# Debug.net
KiCad netlist of a schematic drawn in Altium Designer
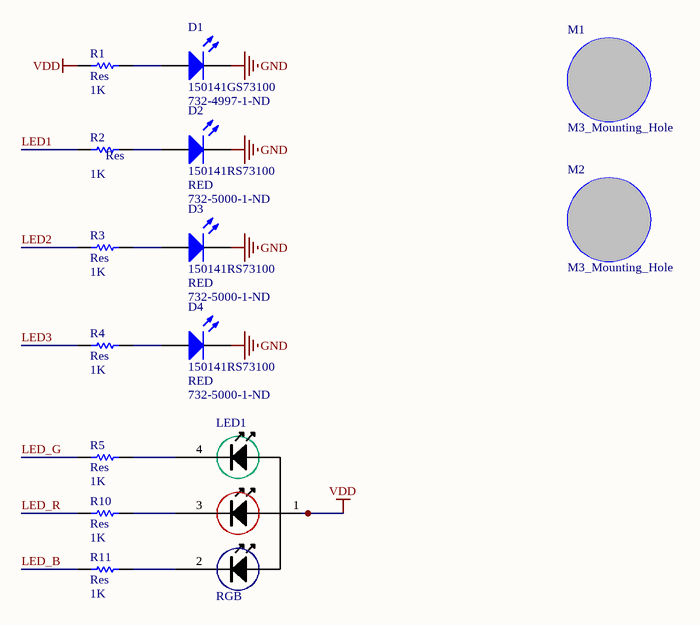
[diagram p0: Debug.SchDoc]

(export (version "E")
  (design (tool "Eeschema 10.0.6"))
  (components
    (comp (ref "D1")
      (value "150141GS73100")
      (footprint "150141RS73100")
      (description "Typical GREEN LED")
      (fields
        (field (name "MANUFACTURER") "Würth Elektronik (Wuerth Elektronik)")
        (field (name "SUPPLIER PART NUMBER 1") "732-4997-1-ND")
      )
      (libsource (lib "FC") (part "150141GS73100"))
    )
    (comp (ref "D2")
      (value "150141RS73100")
      (footprint "150141RS73100")
      (description "Typical RED LED")
      (fields
        (field (name "MANUFACTURER") "Würth Elektronik (Wuerth Elektronik)")
        (field (name "COLOUR") "RED")
        (field (name "SUPPLIER PART NUMBER 2") "732-5000-1-ND")
        (field (name "PUBLISHER") "Altium Limited")
      )
      (libsource (lib "FC") (part "150141RS73100"))
    )
    (comp (ref "D3")
      (value "150141RS73100")
      (footprint "150141RS73100")
      (description "Typical RED LED")
      (fields
        (field (name "MANUFACTURER") "Würth Elektronik (Wuerth Elektronik)")
        (field (name "COLOUR") "RED")
        (field (name "SUPPLIER PART NUMBER 2") "732-5000-1-ND")
        (field (name "PUBLISHER") "Altium Limited")
      )
      (libsource (lib "FC") (part "150141RS73100"))
    )
    (comp (ref "D4")
      (value "150141RS73100")
      (footprint "150141RS73100")
      (description "Typical RED LED")
      (fields
        (field (name "MANUFACTURER") "Würth Elektronik (Wuerth Elektronik)")
        (field (name "COLOUR") "RED")
        (field (name "SUPPLIER PART NUMBER 2") "732-5000-1-ND")
        (field (name "PUBLISHER") "Altium Limited")
      )
      (libsource (lib "FC") (part "150141RS73100"))
    )
    (comp (ref "LED1")
      (value "RGB")
      (footprint "1411LED")
      (description "Wurth RGB LED 1411 pkg")
      (fields
        (field (name "MANUFACTURER") "Wurth Electronics Inc")
        (field (name "MANUFACTURER PART NUMBER") "150141M173100")
      )
      (libsource (lib "FC") (part "LED_150141M173100"))
    )
    (comp (ref "M1")
      (value "M3_Mounting_Hole")
      (footprint "M3_Mounting_Hole")
      (libsource (lib "FC") (part "M3_Mounting_Hole"))
    )
    (comp (ref "M2")
      (value "M3_Mounting_Hole")
      (footprint "M3_Mounting_Hole")
      (libsource (lib "FC") (part "M3_Mounting_Hole"))
    )
    (comp (ref "R1")
      (value "Res")
      (footprint "3216[1206]")
      (description "Surface Mount Resistor")
      (fields (field (name "ALTIUM_VALUE") "1K") (field (name "PUBLISHER") "Altium Limited"))
      (libsource (lib "Resistors") (part "Res"))
    )
    (comp (ref "R2")
      (value "Res")
      (footprint "3216[1206]")
      (description "Surface Mount Resistor")
      (fields (field (name "ALTIUM_VALUE") "1K") (field (name "PUBLISHER") "Altium Limited"))
      (libsource (lib "Resistors") (part "Res"))
    )
    (comp (ref "R3")
      (value "Res")
      (footprint "3216[1206]")
      (description "Surface Mount Resistor")
      (fields (field (name "ALTIUM_VALUE") "1K") (field (name "PUBLISHER") "Altium Limited"))
      (libsource (lib "Resistors") (part "Res"))
    )
    (comp (ref "R4")
      (value "Res")
      (footprint "3216[1206]")
      (description "Surface Mount Resistor")
      (fields (field (name "ALTIUM_VALUE") "1K") (field (name "PUBLISHER") "Altium Limited"))
      (libsource (lib "Resistors") (part "Res"))
    )
    (comp (ref "R5")
      (value "Res")
      (footprint "3216[1206]")
      (description "Surface Mount Resistor")
      (fields (field (name "ALTIUM_VALUE") "1K") (field (name "PUBLISHER") "Altium Limited"))
      (libsource (lib "Resistors") (part "Res"))
    )
    (comp (ref "R10")
      (value "Res")
      (footprint "3216[1206]")
      (description "Surface Mount Resistor")
      (fields (field (name "ALTIUM_VALUE") "1K") (field (name "PUBLISHER") "Altium Limited"))
      (libsource (lib "Resistors") (part "Res"))
    )
    (comp (ref "R11")
      (value "Res")
      (footprint "3216[1206]")
      (description "Surface Mount Resistor")
      (fields (field (name "ALTIUM_VALUE") "1K") (field (name "PUBLISHER") "Altium Limited"))
      (libsource (lib "Resistors") (part "Res"))
    )
  )
  (nets
    (net (code "1") (name "/LED1") (class "Default")
      (node (ref "R2") (pin "1") (pinfunction "1_1") (pintype "passive"))
    )
    (net (code "2") (name "/LED2") (class "Default")
      (node (ref "R3") (pin "1") (pinfunction "1_1") (pintype "passive"))
    )
    (net (code "3") (name "/LED3") (class "Default")
      (node (ref "R4") (pin "1") (pinfunction "1_1") (pintype "passive"))
    )
    (net (code "4") (name "/LED_B") (class "Default")
      (node (ref "R11") (pin "1") (pinfunction "1_1") (pintype "passive"))
    )
    (net (code "5") (name "/LED_G") (class "Default")
      (node (ref "R5") (pin "1") (pinfunction "1_1") (pintype "passive"))
    )
    (net (code "6") (name "/LED_R") (class "Default")
      (node (ref "R10") (pin "1") (pinfunction "1_1") (pintype "passive"))
    )
    (net (code "7") (name "GND") (class "Default")
      (node (ref "D1") (pin "2") (pinfunction "K_2") (pintype "passive"))
      (node (ref "D2") (pin "2") (pinfunction "K_2") (pintype "passive"))
      (node (ref "D3") (pin "2") (pinfunction "K_2") (pintype "passive"))
      (node (ref "D4") (pin "2") (pinfunction "K_2") (pintype "passive"))
    )
    (net (code "8") (name "Net-(D1-A)") (class "Default")
      (node (ref "D1") (pin "1") (pinfunction "A_1") (pintype "passive"))
      (node (ref "R1") (pin "2") (pinfunction "2_2") (pintype "passive"))
    )
    (net (code "9") (name "Net-(D2-A)") (class "Default")
      (node (ref "D2") (pin "1") (pinfunction "A_1") (pintype "passive"))
      (node (ref "R2") (pin "2") (pinfunction "2_2") (pintype "passive"))
    )
    (net (code "10") (name "Net-(D3-A)") (class "Default")
      (node (ref "D3") (pin "1") (pinfunction "A_1") (pintype "passive"))
      (node (ref "R3") (pin "2") (pinfunction "2_2") (pintype "passive"))
    )
    (net (code "11") (name "Net-(D4-A)") (class "Default")
      (node (ref "D4") (pin "1") (pinfunction "A_1") (pintype "passive"))
      (node (ref "R4") (pin "2") (pinfunction "2_2") (pintype "passive"))
    )
    (net (code "12") (name "Net-(LED1-Pad2)") (class "Default")
      (node (ref "LED1") (pin "2") (pinfunction "2_2") (pintype "passive"))
      (node (ref "R11") (pin "2") (pinfunction "2_2") (pintype "passive"))
    )
    (net (code "13") (name "Net-(LED1-Pad3)") (class "Default")
      (node (ref "LED1") (pin "3") (pinfunction "3_3") (pintype "passive"))
      (node (ref "R10") (pin "2") (pinfunction "2_2") (pintype "passive"))
    )
    (net (code "14") (name "Net-(LED1-Pad4)") (class "Default")
      (node (ref "LED1") (pin "4") (pinfunction "4_4") (pintype "passive"))
      (node (ref "R5") (pin "2") (pinfunction "2_2") (pintype "passive"))
    )
    (net (code "15") (name "VDD") (class "Default")
      (node (ref "LED1") (pin "1") (pinfunction "1_1") (pintype "passive"))
      (node (ref "R1") (pin "1") (pinfunction "1_1") (pintype "passive"))
    )
  )
)
